# rs232.net
KiCad netlist of a schematic drawn in Altium Designer
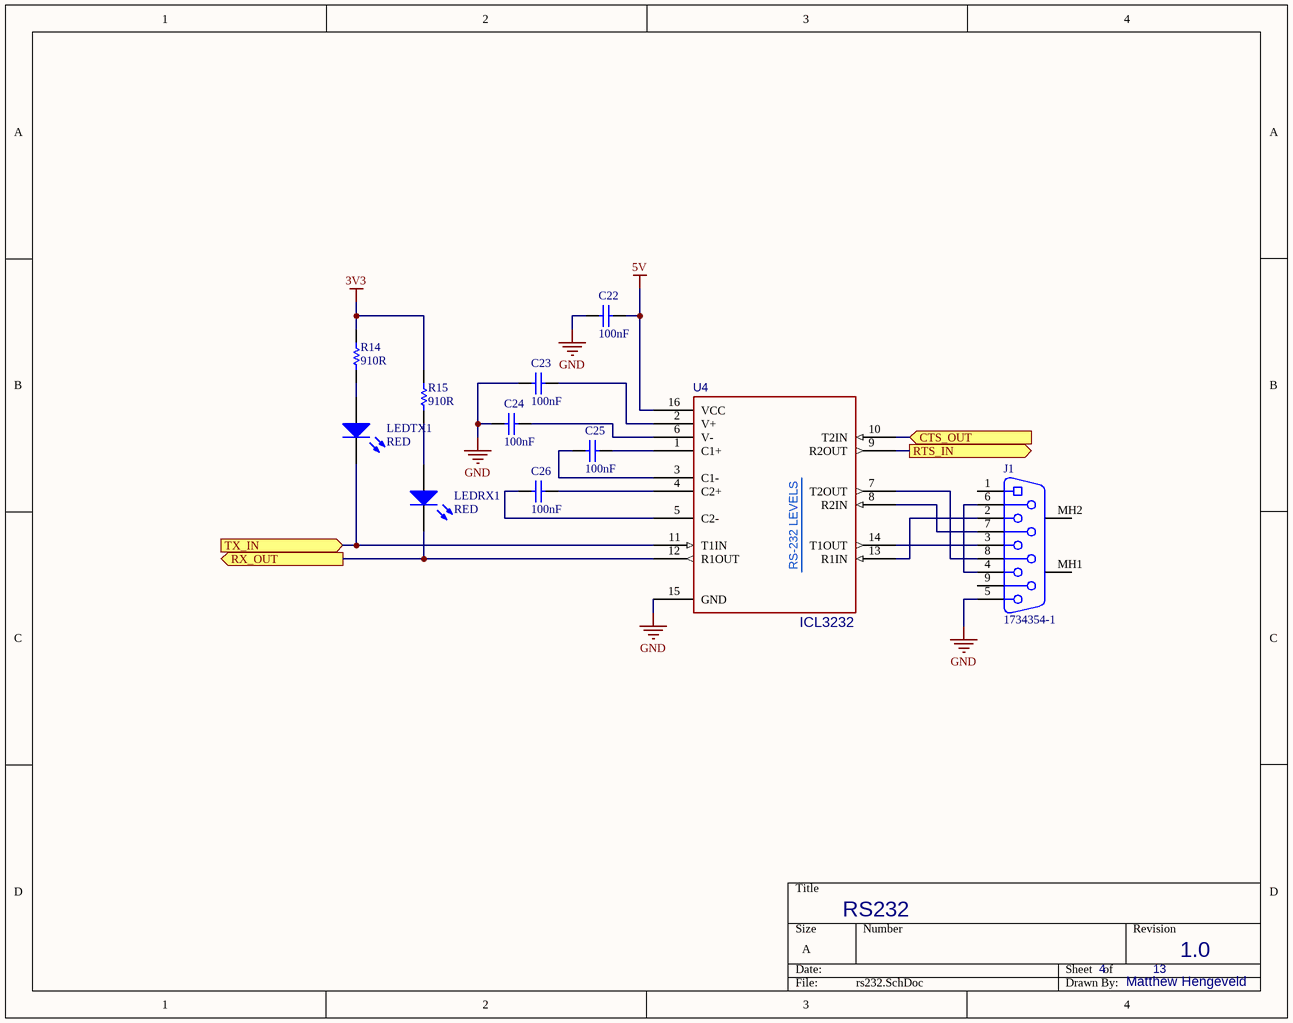
[diagram p0: rs232.SchDoc]

(export (version "E")
  (design (tool "Eeschema 10.0.6"))
  (components
    (comp (ref "C22")
      (value "100nF")
      (footprint "CAPC1608X92X38LL15T08")
      (fields (field (name "PART NUMBER") "VJ0603Y104KNXAO") (field (name "MANUFACTURER") "Vitramon"))
      (libsource (lib "Altium Content Vault") (part "CAP"))
    )
    (comp (ref "C23")
      (value "100nF")
      (footprint "CAPC2013X94X50LL20T25")
      (fields
        (field (name "PART NUMBER") "08055C104K4T2A")
        (field (name "MANUFACTURER") "AVX Interconnect / Elco")
      )
      (libsource (lib "Altium Content Vault") (part "CAP"))
    )
    (comp (ref "C24")
      (value "100nF")
      (footprint "CAPC2013X94X50LL20T25")
      (fields
        (field (name "PART NUMBER") "08055C104K4T2A")
        (field (name "MANUFACTURER") "AVX Interconnect / Elco")
      )
      (libsource (lib "Altium Content Vault") (part "CAP"))
    )
    (comp (ref "C25")
      (value "100nF")
      (footprint "CAPC2013X94X50LL20T25")
      (fields
        (field (name "PART NUMBER") "08055C104K4T2A")
        (field (name "MANUFACTURER") "AVX Interconnect / Elco")
      )
      (libsource (lib "Altium Content Vault") (part "CAP"))
    )
    (comp (ref "C26")
      (value "100nF")
      (footprint "CAPC2013X94X50LL20T25")
      (fields
        (field (name "PART NUMBER") "08055C104K4T2A")
        (field (name "MANUFACTURER") "AVX Interconnect / Elco")
      )
      (libsource (lib "Altium Content Vault") (part "CAP"))
    )
    (comp (ref "J1")
      (value "1734354-1")
      (footprint "TE-1734354-1-9_V")
      (description "D-Subminiature Socket, Pitch 1.385 mm, 9 Position, Height 12.5 mm, Tail Length 3.2 mm, RoHS, Tray")
      (fields (field (name "MANUFACTURER") "TE Connectivity"))
      (libsource (lib "Altium Content Vault") (part "CN-2S-2F-D9"))
    )
    (comp (ref "LEDRX1")
      (value "RED")
      (footprint "0805_A")
      (description "SMD mono-color Chip LED, WL-SMCW, Red")
      (fields (field (name "PARTNUMBER") "150080RS75000") (field (name "MANUFACTURER") "Wuerth Elektronik"))
      (libsource (lib "Altium Content Vault") (part "WE-LED_K1A2-2"))
    )
    (comp (ref "LEDTX1")
      (value "RED")
      (footprint "0805_A")
      (description "SMD mono-color Chip LED, WL-SMCW, Red")
      (fields (field (name "PARTNUMBER") "150080RS75000") (field (name "MANUFACTURER") "Wuerth Elektronik"))
      (libsource (lib "Altium Content Vault") (part "WE-LED_K1A2-2"))
    )
    (comp (ref "R14")
      (value "910R")
      (footprint "RESC1609X50X30LL10T20")
      (fields (field (name "PART NUMBER") "CRCW06034K70JNEA") (field (name "MANUFACTURER") "Vishay Dale"))
      (libsource (lib "Altium Content Vault") (part "RES"))
    )
    (comp (ref "R15")
      (value "910R")
      (footprint "RESC1609X50X30LL10T20")
      (fields (field (name "PART NUMBER") "CRCW06034K70JNEA") (field (name "MANUFACTURER") "Vishay Dale"))
      (libsource (lib "Altium Content Vault") (part "RES"))
    )
    (comp (ref "U4")
      (value "RS232 Transciever")
      (footprint "TSSOP-16")
      (libsource (lib "Hengeveld") (part "ICL3232"))
    )
  )
  (nets
    (net (code "1") (name "/CTS_OUT") (class "Default")
      (node (ref "U4") (pin "10") (pinfunction "T2IN_10") (pintype "input"))
    )
    (net (code "2") (name "/RTS_IN") (class "Default")
      (node (ref "U4") (pin "9") (pinfunction "R2OUT_9") (pintype "output"))
    )
    (net (code "3") (name "/RX_OUT") (class "Default")
      (node (ref "LEDRX1") (pin "1") (pinfunction "K_1") (pintype "passive"))
      (node (ref "U4") (pin "12") (pinfunction "R1OUT_12") (pintype "output"))
    )
    (net (code "4") (name "/TX_IN") (class "Default")
      (node (ref "LEDTX1") (pin "1") (pinfunction "K_1") (pintype "passive"))
      (node (ref "U4") (pin "11") (pinfunction "T1IN_11") (pintype "input"))
    )
    (net (code "5") (name "3V3") (class "Default")
      (node (ref "R14") (pin "2") (pinfunction "2_2") (pintype "passive"))
      (node (ref "R15") (pin "2") (pinfunction "2_2") (pintype "passive"))
    )
    (net (code "6") (name "5V") (class "Default")
      (node (ref "C22") (pin "2") (pinfunction "2_2") (pintype "passive"))
      (node (ref "U4") (pin "16") (pinfunction "VCC_16") (pintype "power_in"))
    )
    (net (code "7") (name "GND") (class "Default")
      (node (ref "C22") (pin "1") (pinfunction "1_1") (pintype "passive"))
      (node (ref "C23") (pin "2") (pinfunction "2_2") (pintype "passive"))
      (node (ref "C24") (pin "2") (pinfunction "2_2") (pintype "passive"))
      (node (ref "J1") (pin "5") (pinfunction "5_5") (pintype "passive"))
      (node (ref "U4") (pin "15") (pinfunction "GND_15") (pintype "power_in"))
    )
    (net (code "8") (name "Net-(J1-Pad4)") (class "Default")
      (node (ref "J1") (pin "4") (pinfunction "4_4") (pintype "passive"))
      (node (ref "J1") (pin "6") (pinfunction "6_6") (pintype "passive"))
    )
    (net (code "9") (name "Net-(LEDRX1-A)") (class "Default")
      (node (ref "LEDRX1") (pin "2") (pinfunction "A_2") (pintype "passive"))
      (node (ref "R15") (pin "1") (pinfunction "1_1") (pintype "passive"))
    )
    (net (code "10") (name "Net-(LEDTX1-A)") (class "Default")
      (node (ref "LEDTX1") (pin "2") (pinfunction "A_2") (pintype "passive"))
      (node (ref "R14") (pin "1") (pinfunction "1_1") (pintype "passive"))
    )
    (net (code "11") (name "Net-(U4-C1+)") (class "Default")
      (node (ref "C25") (pin "1") (pinfunction "1_1") (pintype "passive"))
      (node (ref "U4") (pin "1") (pinfunction "C1+_1") (pintype "power_in"))
    )
    (net (code "12") (name "Net-(U4-C1-)") (class "Default")
      (node (ref "C25") (pin "2") (pinfunction "2_2") (pintype "passive"))
      (node (ref "U4") (pin "3") (pinfunction "C1-_3") (pintype "power_in"))
    )
    (net (code "13") (name "Net-(U4-C2+)") (class "Default")
      (node (ref "C26") (pin "2") (pinfunction "2_2") (pintype "passive"))
      (node (ref "U4") (pin "4") (pinfunction "C2+_4") (pintype "power_in"))
    )
    (net (code "14") (name "Net-(U4-C2-)") (class "Default")
      (node (ref "C26") (pin "1") (pinfunction "1_1") (pintype "passive"))
      (node (ref "U4") (pin "5") (pinfunction "C2-_5") (pintype "power_in"))
    )
    (net (code "15") (name "Net-(U4-R1IN)") (class "Default")
      (node (ref "J1") (pin "2") (pinfunction "2_2") (pintype "passive"))
      (node (ref "U4") (pin "13") (pinfunction "R1IN_13") (pintype "input"))
    )
    (net (code "16") (name "Net-(U4-R2IN)") (class "Default")
      (node (ref "J1") (pin "7") (pinfunction "7_7") (pintype "passive"))
      (node (ref "U4") (pin "8") (pinfunction "R2IN_8") (pintype "input"))
    )
    (net (code "17") (name "Net-(U4-T1OUT)") (class "Default")
      (node (ref "J1") (pin "3") (pinfunction "3_3") (pintype "passive"))
      (node (ref "U4") (pin "14") (pinfunction "T1OUT_14") (pintype "output"))
    )
    (net (code "18") (name "Net-(U4-T2OUT)") (class "Default")
      (node (ref "J1") (pin "8") (pinfunction "8_8") (pintype "passive"))
      (node (ref "U4") (pin "7") (pinfunction "T2OUT_7") (pintype "output"))
    )
    (net (code "19") (name "Net-(U4-V+)") (class "Default")
      (node (ref "C23") (pin "1") (pinfunction "1_1") (pintype "passive"))
      (node (ref "U4") (pin "2") (pinfunction "V+_2") (pintype "power_in"))
    )
    (net (code "20") (name "Net-(U4-V-)") (class "Default")
      (node (ref "C24") (pin "1") (pinfunction "1_1") (pintype "passive"))
      (node (ref "U4") (pin "6") (pinfunction "V-_6") (pintype "power_in"))
    )
    (net (code "21") (name "unconnected-(J1-Pad1)") (class "Default")
      (node (ref "J1") (pin "1") (pinfunction "1_1") (pintype "passive"))
    )
    (net (code "22") (name "unconnected-(J1-Pad9)") (class "Default")
      (node (ref "J1") (pin "9") (pinfunction "9_9") (pintype "passive"))
    )
    (net (code "23") (name "unconnected-(J1-PadMH1)") (class "Default")
      (node (ref "J1") (pin "MH1") (pinfunction "MH1_MH1") (pintype "passive"))
    )
    (net (code "24") (name "unconnected-(J1-PadMH2)") (class "Default")
      (node (ref "J1") (pin "MH2") (pinfunction "MH2_MH2") (pintype "passive"))
    )
  )
)
